# cc-driver-pico-host-board-as-built.net
KiCad netlist of a schematic drawn in EAGLE
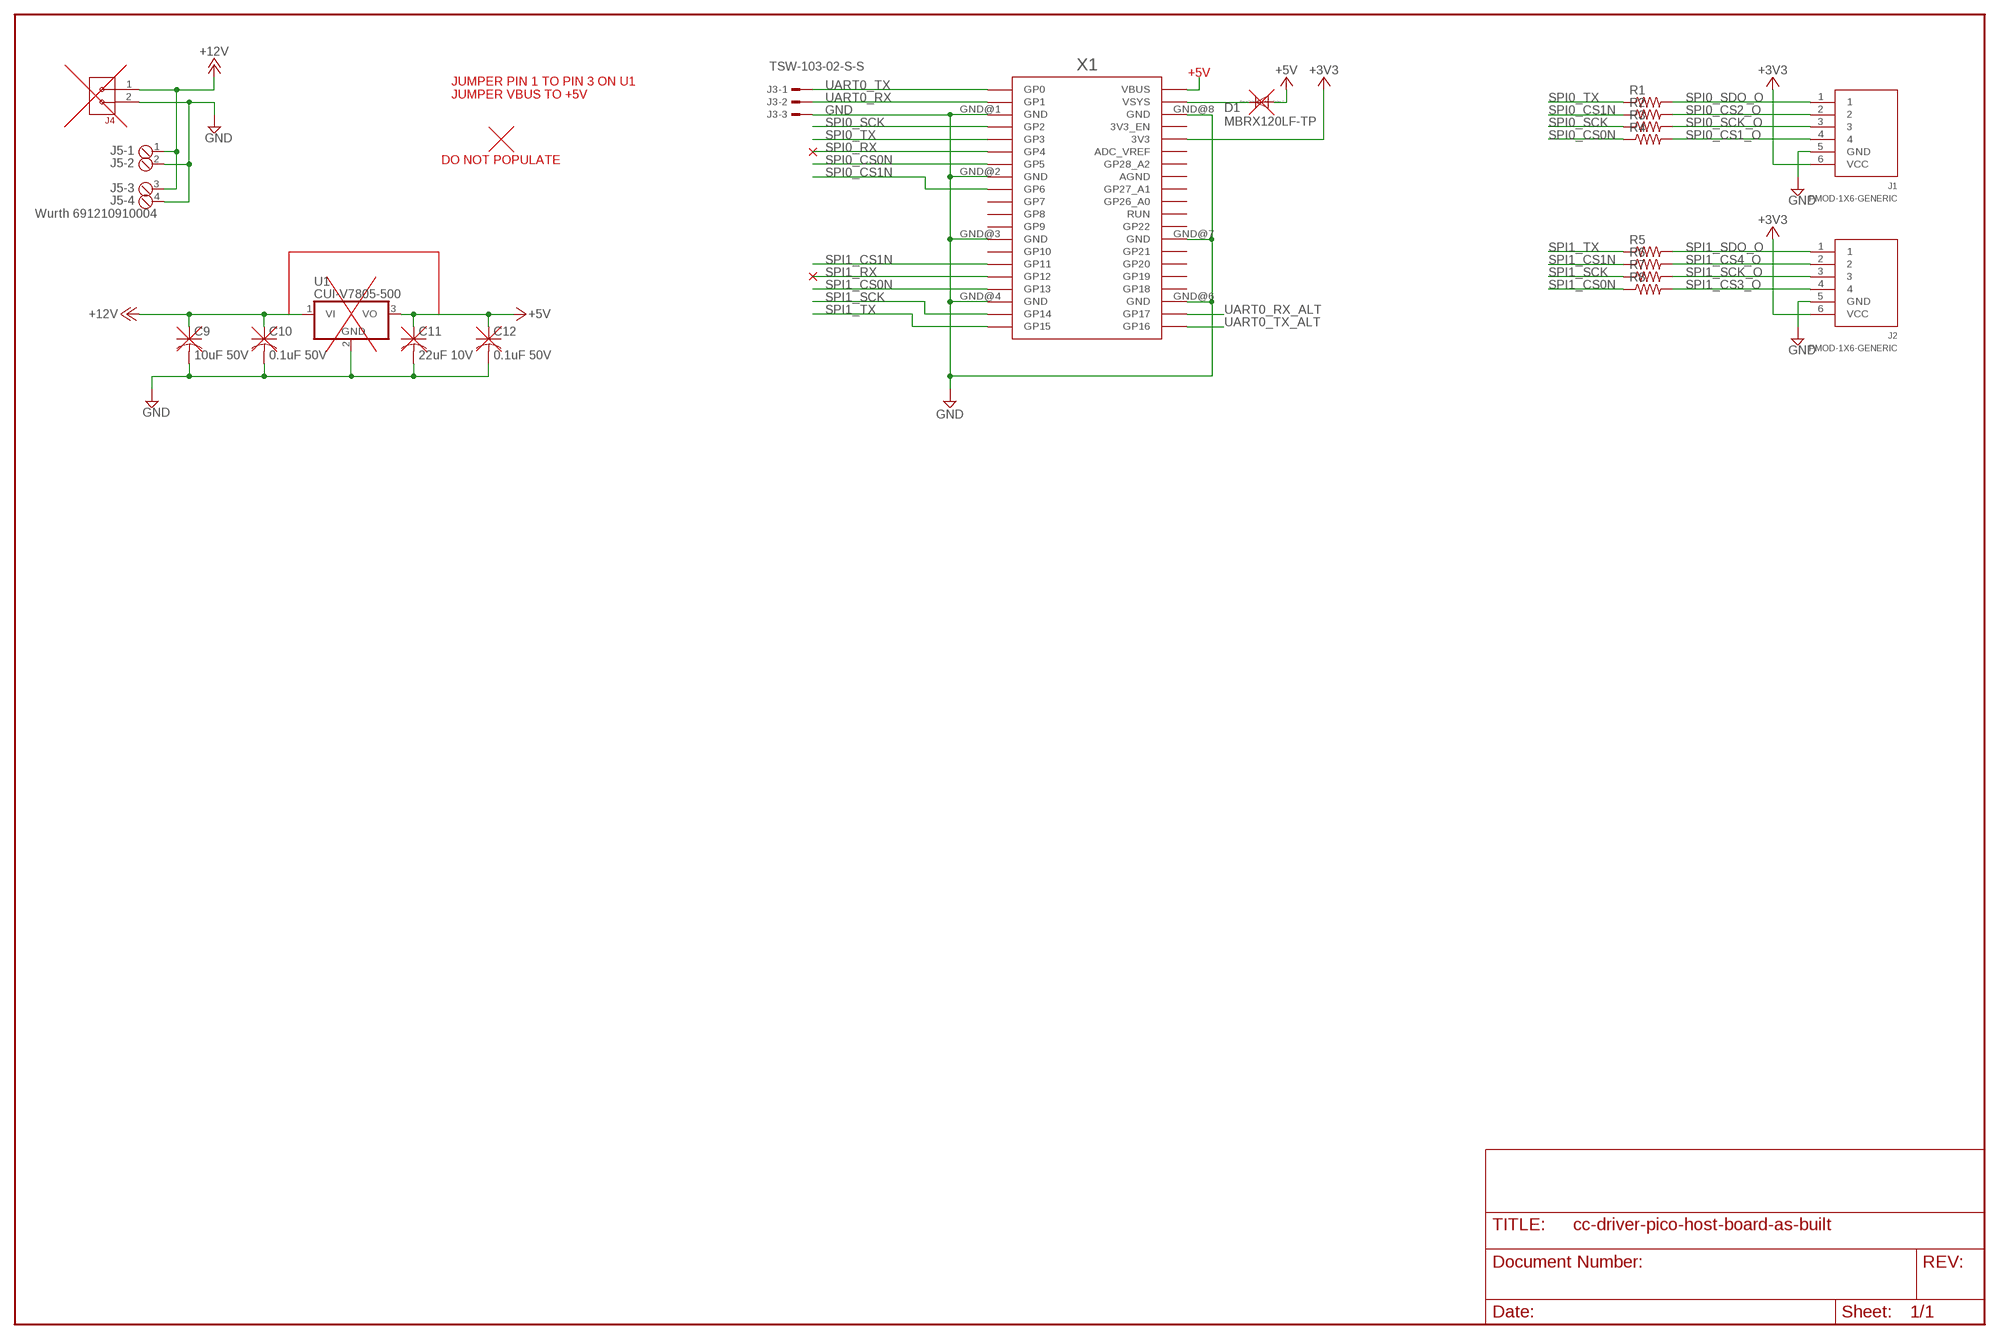
[diagram p0: schematic, sheet 1]

(export (version "E")
  (design (tool "Eeschema 10.0.6"))
  (components
    (comp (ref "C9")
      (value "10uF 50V")
      (footprint "eagle-import:C1210K")
      (fields (field (name "MFR") "KEMET") (field (name "MFR_PART_NO") "C1210C106K5RACTU"))
      (libsource (lib "eagle-import") (part "C-USC1210K"))
    )
    (comp (ref "C10")
      (value "0.1uF 50V")
      (footprint "eagle-import:C1206K")
      (fields (field (name "MFR") "KEMET") (field (name "MFR_PART_NO") "C1206S104M5RACTU"))
      (libsource (lib "eagle-import") (part "C-USC1206K"))
    )
    (comp (ref "C11")
      (value "22uF 10V")
      (footprint "eagle-import:C1206K")
      (fields (field (name "MFR") "KEMET") (field (name "MFR_PART_NO") "C1206C226K8RAC7800"))
      (libsource (lib "eagle-import") (part "C-USC1206K"))
    )
    (comp (ref "C12")
      (value "0.1uF 50V")
      (footprint "eagle-import:C1206K")
      (fields (field (name "MFR") "KEMET") (field (name "MFR_PART_NO") "C1206S104M5RACTU"))
      (libsource (lib "eagle-import") (part "C-USC1206K"))
    )
    (comp (ref "D1")
      (value "MBRX120LF-TP")
      (footprint "eagle-import:SOD123")
      (libsource (lib "eagle-import") (part "MBR0520LT"))
    )
    (comp (ref "J1")
      (value "PMOD-1X6-GENERIC")
      (footprint "eagle-import:CON-PMOD-1X6")
      (libsource (lib "eagle-import") (part "PMOD-1X6-GENERIC"))
    )
    (comp (ref "J2")
      (value "PMOD-1X6-GENERIC")
      (footprint "eagle-import:CON-PMOD-1X6")
      (libsource (lib "eagle-import") (part "PMOD-1X6-GENERIC"))
    )
    (comp (ref "J3")
      (value "TSW-103-02-S-S")
      (footprint "eagle-import:TSW-103-02-S-S")
      (libsource (lib "eagle-import") (part "TSW-103-02-S-S"))
    )
    (comp (ref "J4")
      (value "CON-3.81MM-1X2-PHOENIX")
      (footprint "eagle-import:CON-PHOENIX-3.81-1X2-RA")
      (libsource (lib "eagle-import") (part "CON-3.81MM-1X2-PHOENIX"))
    )
    (comp (ref "J5")
      (value "Wurth 691210910004")
      (footprint "eagle-import:4POL254")
      (libsource (lib "eagle-import") (part "MPT4"))
    )
    (comp (ref "R1")
      (value "R-US_R0603")
      (footprint "eagle-import:R0603")
      (libsource (lib "eagle-import") (part "R-US_R0603"))
    )
    (comp (ref "R2")
      (value "R-US_R0603")
      (footprint "eagle-import:R0603")
      (libsource (lib "eagle-import") (part "R-US_R0603"))
    )
    (comp (ref "R3")
      (value "R-US_R0603")
      (footprint "eagle-import:R0603")
      (libsource (lib "eagle-import") (part "R-US_R0603"))
    )
    (comp (ref "R4")
      (value "R-US_R0603")
      (footprint "eagle-import:R0603")
      (libsource (lib "eagle-import") (part "R-US_R0603"))
    )
    (comp (ref "R5")
      (value "R-US_R0603")
      (footprint "eagle-import:R0603")
      (libsource (lib "eagle-import") (part "R-US_R0603"))
    )
    (comp (ref "R6")
      (value "R-US_R0603")
      (footprint "eagle-import:R0603")
      (libsource (lib "eagle-import") (part "R-US_R0603"))
    )
    (comp (ref "R7")
      (value "R-US_R0603")
      (footprint "eagle-import:R0603")
      (libsource (lib "eagle-import") (part "R-US_R0603"))
    )
    (comp (ref "R8")
      (value "R-US_R0603")
      (footprint "eagle-import:R0603")
      (libsource (lib "eagle-import") (part "R-US_R0603"))
    )
    (comp (ref "U1")
      (value "CUI-V7805-500")
      (footprint "eagle-import:CUI-78XX-500")
      (libsource (lib "eagle-import") (part "CUI-V7803-500"))
    )
    (comp (ref "X1")
      (value "RPI_PICO_IG-TH")
      (footprint "eagle-import:RPI_PICO_TH")
      (libsource (lib "eagle-import") (part "RPI_PICO_IG-TH"))
    )
  )
  (nets
    (net (code "1") (name "+3V3") (class "Default")
      (node (ref "J1") (pin "6") (pinfunction "VCC_6") (pintype "bidirectional"))
      (node (ref "J2") (pin "6") (pinfunction "VCC_6") (pintype "bidirectional"))
      (node (ref "X1") (pin "3V3") (pinfunction "3V3_3V3") (pintype "bidirectional"))
    )
    (net (code "2") (name "+5V") (class "Default")
      (node (ref "C11") (pin "1") (pinfunction "1_1") (pintype "passive"))
      (node (ref "C12") (pin "1") (pinfunction "1_1") (pintype "passive"))
      (node (ref "D1") (pin "A") (pinfunction "A_A") (pintype "passive"))
      (node (ref "U1") (pin "3") (pinfunction "VO_3") (pintype "passive"))
    )
    (net (code "3") (name "+12V") (class "Default")
      (node (ref "C10") (pin "1") (pinfunction "1_1") (pintype "passive"))
      (node (ref "C9") (pin "1") (pinfunction "1_1") (pintype "passive"))
      (node (ref "J4") (pin "1") (pinfunction "1_1") (pintype "bidirectional"))
      (node (ref "J5") (pin "1") (pinfunction "1_1") (pintype "passive"))
      (node (ref "J5") (pin "3") (pinfunction "1_3") (pintype "passive"))
      (node (ref "U1") (pin "1") (pinfunction "VI_1") (pintype "input"))
    )
    (net (code "4") (name "/SPI0_CS0N") (class "Default")
      (node (ref "R4") (pin "1") (pinfunction "1_1") (pintype "passive"))
      (node (ref "X1") (pin "GP5") (pinfunction "GP5_GP5") (pintype "bidirectional"))
    )
    (net (code "5") (name "/SPI0_CS1N") (class "Default")
      (node (ref "R2") (pin "1") (pinfunction "1_1") (pintype "passive"))
      (node (ref "X1") (pin "GP6") (pinfunction "GP6_GP6") (pintype "bidirectional"))
    )
    (net (code "6") (name "/SPI0_CS1_O") (class "Default")
      (node (ref "J1") (pin "4") (pinfunction "4_4") (pintype "bidirectional"))
      (node (ref "R4") (pin "2") (pinfunction "2_2") (pintype "passive"))
    )
    (net (code "7") (name "/SPI0_CS2_O") (class "Default")
      (node (ref "J1") (pin "2") (pinfunction "2_2") (pintype "bidirectional"))
      (node (ref "R2") (pin "2") (pinfunction "2_2") (pintype "passive"))
    )
    (net (code "8") (name "/SPI0_RX") (class "Default")
      (node (ref "X1") (pin "GP4") (pinfunction "GP4_GP4") (pintype "bidirectional"))
    )
    (net (code "9") (name "/SPI0_SCK") (class "Default")
      (node (ref "R3") (pin "1") (pinfunction "1_1") (pintype "passive"))
      (node (ref "X1") (pin "GP2") (pinfunction "GP2_GP2") (pintype "bidirectional"))
    )
    (net (code "10") (name "/SPI0_SCK_O") (class "Default")
      (node (ref "J1") (pin "3") (pinfunction "3_3") (pintype "bidirectional"))
      (node (ref "R3") (pin "2") (pinfunction "2_2") (pintype "passive"))
    )
    (net (code "11") (name "/SPI0_SDO_O") (class "Default")
      (node (ref "J1") (pin "1") (pinfunction "1_1") (pintype "bidirectional"))
      (node (ref "R1") (pin "2") (pinfunction "2_2") (pintype "passive"))
    )
    (net (code "12") (name "/SPI0_TX") (class "Default")
      (node (ref "R1") (pin "1") (pinfunction "1_1") (pintype "passive"))
      (node (ref "X1") (pin "GP3") (pinfunction "GP3_GP3") (pintype "bidirectional"))
    )
    (net (code "13") (name "/SPI1_CS0N") (class "Default")
      (node (ref "R8") (pin "1") (pinfunction "1_1") (pintype "passive"))
      (node (ref "X1") (pin "GP13") (pinfunction "GP13_GP13") (pintype "bidirectional"))
    )
    (net (code "14") (name "/SPI1_CS1N") (class "Default")
      (node (ref "R6") (pin "1") (pinfunction "1_1") (pintype "passive"))
      (node (ref "X1") (pin "GP11") (pinfunction "GP11_GP11") (pintype "bidirectional"))
    )
    (net (code "15") (name "/SPI1_CS3_O") (class "Default")
      (node (ref "J2") (pin "4") (pinfunction "4_4") (pintype "bidirectional"))
      (node (ref "R8") (pin "2") (pinfunction "2_2") (pintype "passive"))
    )
    (net (code "16") (name "/SPI1_CS4_O") (class "Default")
      (node (ref "J2") (pin "2") (pinfunction "2_2") (pintype "bidirectional"))
      (node (ref "R6") (pin "2") (pinfunction "2_2") (pintype "passive"))
    )
    (net (code "17") (name "/SPI1_RX") (class "Default")
      (node (ref "X1") (pin "GP12") (pinfunction "GP12_GP12") (pintype "bidirectional"))
    )
    (net (code "18") (name "/SPI1_SCK") (class "Default")
      (node (ref "R7") (pin "1") (pinfunction "1_1") (pintype "passive"))
      (node (ref "X1") (pin "GP14") (pinfunction "GP14_GP14") (pintype "bidirectional"))
    )
    (net (code "19") (name "/SPI1_SCK_O") (class "Default")
      (node (ref "J2") (pin "3") (pinfunction "3_3") (pintype "bidirectional"))
      (node (ref "R7") (pin "2") (pinfunction "2_2") (pintype "passive"))
    )
    (net (code "20") (name "/SPI1_SDO_O") (class "Default")
      (node (ref "J2") (pin "1") (pinfunction "1_1") (pintype "bidirectional"))
      (node (ref "R5") (pin "2") (pinfunction "2_2") (pintype "passive"))
    )
    (net (code "21") (name "/SPI1_TX") (class "Default")
      (node (ref "R5") (pin "1") (pinfunction "1_1") (pintype "passive"))
      (node (ref "X1") (pin "GP15") (pinfunction "GP15_GP15") (pintype "bidirectional"))
    )
    (net (code "22") (name "/UART0_RX") (class "Default")
      (node (ref "J3") (pin "2") (pinfunction "1_2") (pintype "passive"))
      (node (ref "X1") (pin "GP1") (pinfunction "GP1_GP1") (pintype "bidirectional"))
    )
    (net (code "23") (name "/UART0_RX_ALT") (class "Default")
      (node (ref "X1") (pin "GP17") (pinfunction "GP17_GP17") (pintype "bidirectional"))
    )
    (net (code "24") (name "/UART0_TX") (class "Default")
      (node (ref "J3") (pin "1") (pinfunction "1_1") (pintype "passive"))
      (node (ref "X1") (pin "GP0") (pinfunction "GP0_GP0") (pintype "bidirectional"))
    )
    (net (code "25") (name "/UART0_TX_ALT") (class "Default")
      (node (ref "X1") (pin "GP16") (pinfunction "GP16_GP16") (pintype "bidirectional"))
    )
    (net (code "26") (name "GND") (class "Default")
      (node (ref "C10") (pin "2") (pinfunction "2_2") (pintype "passive"))
      (node (ref "C11") (pin "2") (pinfunction "2_2") (pintype "passive"))
      (node (ref "C12") (pin "2") (pinfunction "2_2") (pintype "passive"))
      (node (ref "C9") (pin "2") (pinfunction "2_2") (pintype "passive"))
      (node (ref "J1") (pin "5") (pinfunction "GND_5") (pintype "power_in"))
      (node (ref "J2") (pin "5") (pinfunction "GND_5") (pintype "power_in"))
      (node (ref "J3") (pin "3") (pinfunction "1_3") (pintype "passive"))
      (node (ref "J4") (pin "2") (pinfunction "2_2") (pintype "bidirectional"))
      (node (ref "J5") (pin "2") (pinfunction "1_2") (pintype "passive"))
      (node (ref "J5") (pin "4") (pinfunction "1_4") (pintype "passive"))
      (node (ref "U1") (pin "2") (pinfunction "GND_2") (pintype "passive"))
      (node (ref "X1") (pin "GND@1") (pinfunction "GND_GND@1") (pintype "bidirectional"))
      (node (ref "X1") (pin "GND@2") (pinfunction "GND_GND@2") (pintype "bidirectional"))
      (node (ref "X1") (pin "GND@3") (pinfunction "GND_GND@3") (pintype "bidirectional"))
      (node (ref "X1") (pin "GND@4") (pinfunction "GND_GND@4") (pintype "bidirectional"))
      (node (ref "X1") (pin "GND@6") (pinfunction "GND_GND@6") (pintype "bidirectional"))
      (node (ref "X1") (pin "GND@7") (pinfunction "GND_GND@7") (pintype "bidirectional"))
      (node (ref "X1") (pin "GND@8") (pinfunction "GND_GND@8") (pintype "bidirectional"))
    )
    (net (code "27") (name "Net-(D1-PadC)") (class "Default")
      (node (ref "D1") (pin "C") (pinfunction "C_C") (pintype "passive"))
      (node (ref "X1") (pin "VSYS") (pinfunction "VSYS_VSYS") (pintype "bidirectional"))
    )
    (net (code "28") (name "unconnected-(X1-Pad3V3_EN)") (class "Default")
      (node (ref "X1") (pin "3V3_EN") (pinfunction "3V3_EN_3V3_EN") (pintype "bidirectional"))
    )
    (net (code "29") (name "unconnected-(X1-PadADC_VREF)") (class "Default")
      (node (ref "X1") (pin "ADC_VREF") (pinfunction "ADC_VREF_ADC_VREF") (pintype "bidirectional"))
    )
    (net (code "30") (name "unconnected-(X1-PadAGND)") (class "Default")
      (node (ref "X1") (pin "AGND") (pinfunction "AGND_AGND") (pintype "bidirectional"))
    )
    (net (code "31") (name "unconnected-(X1-PadGP7)") (class "Default")
      (node (ref "X1") (pin "GP7") (pinfunction "GP7_GP7") (pintype "bidirectional"))
    )
    (net (code "32") (name "unconnected-(X1-PadGP8)") (class "Default")
      (node (ref "X1") (pin "GP8") (pinfunction "GP8_GP8") (pintype "bidirectional"))
    )
    (net (code "33") (name "unconnected-(X1-PadGP9)") (class "Default")
      (node (ref "X1") (pin "GP9") (pinfunction "GP9_GP9") (pintype "bidirectional"))
    )
    (net (code "34") (name "unconnected-(X1-PadGP10)") (class "Default")
      (node (ref "X1") (pin "GP10") (pinfunction "GP10_GP10") (pintype "bidirectional"))
    )
    (net (code "35") (name "unconnected-(X1-PadGP18)") (class "Default")
      (node (ref "X1") (pin "GP18") (pinfunction "GP18_GP18") (pintype "bidirectional"))
    )
    (net (code "36") (name "unconnected-(X1-PadGP19)") (class "Default")
      (node (ref "X1") (pin "GP19") (pinfunction "GP19_GP19") (pintype "bidirectional"))
    )
    (net (code "37") (name "unconnected-(X1-PadGP20)") (class "Default")
      (node (ref "X1") (pin "GP20") (pinfunction "GP20_GP20") (pintype "bidirectional"))
    )
    (net (code "38") (name "unconnected-(X1-PadGP21)") (class "Default")
      (node (ref "X1") (pin "GP21") (pinfunction "GP21_GP21") (pintype "bidirectional"))
    )
    (net (code "39") (name "unconnected-(X1-PadGP22)") (class "Default")
      (node (ref "X1") (pin "GP22") (pinfunction "GP22_GP22") (pintype "bidirectional"))
    )
    (net (code "40") (name "unconnected-(X1-PadGP26_A0)") (class "Default")
      (node (ref "X1") (pin "GP26_A0") (pinfunction "GP26_A0_GP26_A0") (pintype "bidirectional"))
    )
    (net (code "41") (name "unconnected-(X1-PadGP27_A1)") (class "Default")
      (node (ref "X1") (pin "GP27_A1") (pinfunction "GP27_A1_GP27_A1") (pintype "bidirectional"))
    )
    (net (code "42") (name "unconnected-(X1-PadGP28_A2)") (class "Default")
      (node (ref "X1") (pin "GP28_A2") (pinfunction "GP28_A2_GP28_A2") (pintype "bidirectional"))
    )
    (net (code "43") (name "unconnected-(X1-PadRUN)") (class "Default")
      (node (ref "X1") (pin "RUN") (pinfunction "RUN_RUN") (pintype "bidirectional"))
    )
    (net (code "44") (name "unconnected-(X1-PadVBUS)") (class "Default")
      (node (ref "X1") (pin "VBUS") (pinfunction "VBUS_VBUS") (pintype "bidirectional"))
    )
  )
)
